# Interface.net
KiCad netlist of a schematic drawn in Altium Designer
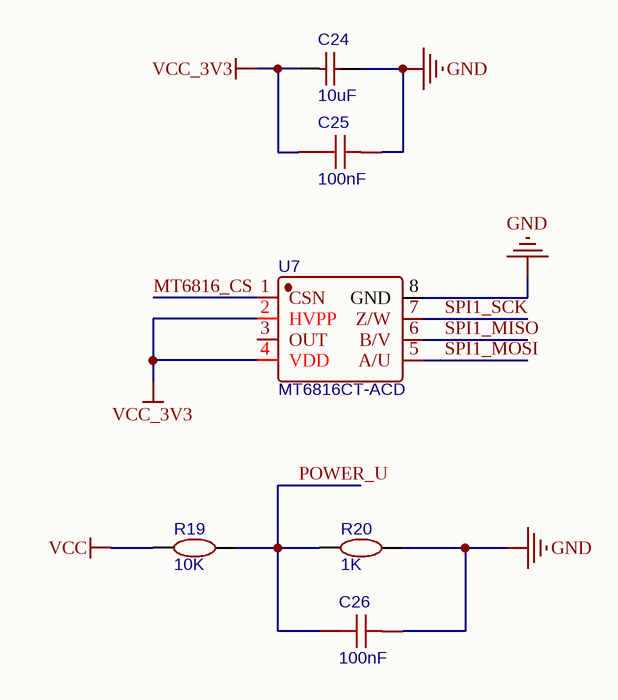
[diagram p0: Interface.SchDoc]

(export (version "E")
  (design (tool "Eeschema 10.0.6"))
  (components
    (comp (ref "C24")
      (value "10uF")
      (footprint "C1206")
      (fields
        (field (name "BOM_MANUFACTURER PART") "CL31A106KBHNNNE")
        (field (name "BOM_SUPPLIER PART") "C13585")
      )
      (libsource (lib "10uF") (part "10uF"))
    )
    (comp (ref "C25")
      (value "100nF")
      (footprint "C0603")
      (fields
        (field (name "BOM_MANUFACTURER PART") "CL10B104KB8NNNC")
        (field (name "BOM_SUPPLIER PART") "C1591")
      )
      (libsource (lib "0.1uF") (part "100nF"))
    )
    (comp (ref "C26")
      (value "100nF")
      (footprint "C0603")
      (fields
        (field (name "BOM_MANUFACTURER PART") "CL10B104KB8NNNC")
        (field (name "BOM_SUPPLIER PART") "C1591")
      )
      (libsource (lib "0.1uF") (part "100nF"))
    )
    (comp (ref "R19")
      (value "10K")
      (footprint "R0603")
      (fields
        (field (name "BOM_MANUFACTURER PART") "0603WAF1002T5E")
        (field (name "BOM_SUPPLIER PART") "C25804")
      )
      (libsource (lib "10K") (part "10K"))
    )
    (comp (ref "R20")
      (value "1K")
      (footprint "R0603")
      (fields
        (field (name "BOM_MANUFACTURER PART") "0603WAF1001T5E")
        (field (name "BOM_SUPPLIER PART") "C21190")
      )
      (libsource (lib "1K") (part "1K"))
    )
    (comp (ref "U7")
      (value "MT6816CT-ACD")
      (footprint "SOP-8_L5.0-W4.0-P1.27-LS6.0-BL")
      (fields (field (name "BOM_SUPPLIER PART") "C879560") (field (name "CONTRIBUTOR") "LCSC"))
      (libsource (lib "MT6816") (part "MT6816CT-ACD"))
    )
  )
  (nets
    (net (code "1") (name "/MT6816_CS") (class "Default")
      (node (ref "U7") (pin "1") (pinfunction "CSN_1") (pintype "passive"))
    )
    (net (code "2") (name "/POWER_U") (class "Default")
      (node (ref "C26") (pin "1") (pinfunction "1_1") (pintype "passive"))
      (node (ref "R19") (pin "2") (pinfunction "2_2") (pintype "passive"))
      (node (ref "R20") (pin "1") (pinfunction "1_1") (pintype "passive"))
    )
    (net (code "3") (name "/SPI1_MISO") (class "Default")
      (node (ref "U7") (pin "6") (pinfunction "B/V_6") (pintype "passive"))
    )
    (net (code "4") (name "/SPI1_MOSI") (class "Default")
      (node (ref "U7") (pin "5") (pinfunction "A/U_5") (pintype "passive"))
    )
    (net (code "5") (name "/SPI1_SCK") (class "Default")
      (node (ref "U7") (pin "7") (pinfunction "Z/W_7") (pintype "passive"))
    )
    (net (code "6") (name "GND") (class "Default")
      (node (ref "C24") (pin "2") (pinfunction "2_2") (pintype "passive"))
      (node (ref "C25") (pin "2") (pinfunction "2_2") (pintype "passive"))
      (node (ref "C26") (pin "2") (pinfunction "2_2") (pintype "passive"))
      (node (ref "R20") (pin "2") (pinfunction "2_2") (pintype "passive"))
      (node (ref "U7") (pin "8") (pinfunction "GND_8") (pintype "passive"))
    )
    (net (code "7") (name "VCC") (class "Default")
      (node (ref "R19") (pin "1") (pinfunction "1_1") (pintype "passive"))
    )
    (net (code "8") (name "VCC_3V3") (class "Default")
      (node (ref "C24") (pin "1") (pinfunction "1_1") (pintype "passive"))
      (node (ref "C25") (pin "1") (pinfunction "1_1") (pintype "passive"))
      (node (ref "U7") (pin "2") (pinfunction "HVPP_2") (pintype "passive"))
      (node (ref "U7") (pin "4") (pinfunction "VDD_4") (pintype "passive"))
    )
    (net (code "9") (name "unconnected-(U7-OUT-Pad3)") (class "Default")
      (node (ref "U7") (pin "3") (pinfunction "OUT_3") (pintype "passive"))
    )
  )
)
